# Regelaar.net
KiCad netlist of a schematic drawn in Altium Designer
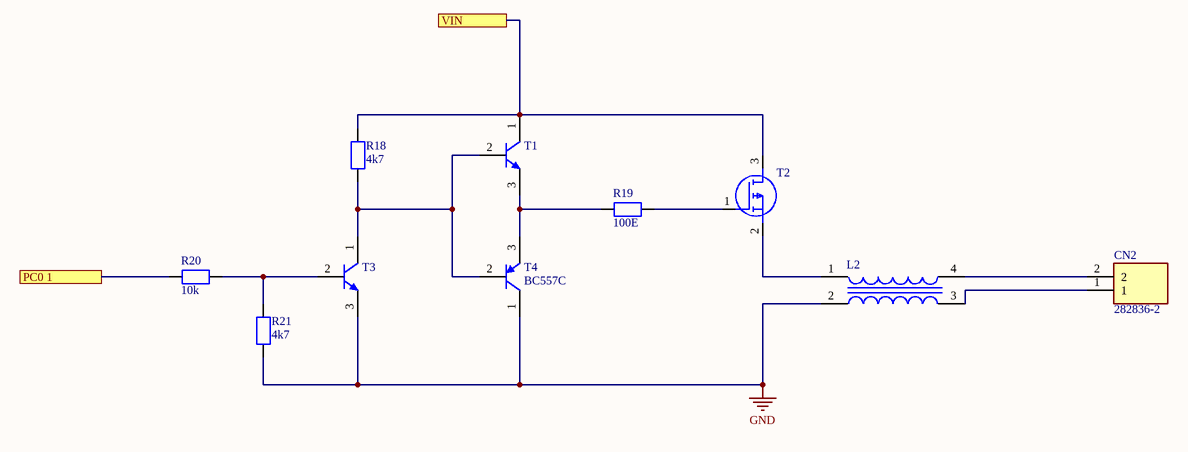
[diagram p0: Regelaar.SchDoc]

(export (version "E")
  (design (tool "Eeschema 10.0.6"))
  (components
    (comp (ref "CN2")
      (value "282836-2")
      (footprint "Schroefconnector 2 Pin")
      (description "Connector")
      (libsource (lib "Soldeerstation") (part "Schroefconnector 2 Pin L"))
    )
    (comp (ref "L2")
      (value "Smoorspoel commom mode")
      (footprint "smoorspoel Common mode")
      (description "Transformer CM2545X171B-10")
      (fields (field (name "MANUFACTURER_PART_NUMBER") "CM2545X171B-10"))
      (libsource (lib "Soldeerstation") (part "Smoorspoel commom mode"))
    )
    (comp (ref "R18")
      (value "4k7")
      (footprint "Resistor")
      (description "Resistor")
      (fields (field (name "MANUFACTURER") "Vishay Dale") (field (name "PART NUMBER") "CRCW08050000Z0EA"))
      (libsource (lib "Soldeerstation") (part "Resistor"))
    )
    (comp (ref "R19")
      (value "100E")
      (footprint "Resistor")
      (description "Resistor")
      (fields (field (name "MANUFACTURER") "Vishay Dale") (field (name "PART NUMBER") "CRCW08050000Z0EA"))
      (libsource (lib "Soldeerstation") (part "Resistor"))
    )
    (comp (ref "R20")
      (value "10k")
      (footprint "Resistor")
      (description "Resistor")
      (fields (field (name "MANUFACTURER") "Vishay Dale") (field (name "PART NUMBER") "CRCW08050000Z0EA"))
      (libsource (lib "Soldeerstation") (part "Resistor"))
    )
    (comp (ref "R21")
      (value "4k7")
      (footprint "Resistor")
      (description "Resistor")
      (fields (field (name "MANUFACTURER") "Vishay Dale") (field (name "PART NUMBER") "CRCW08050000Z0EA"))
      (libsource (lib "Soldeerstation") (part "Resistor"))
    )
    (comp (ref "T1")
      (value "BC547CZL1G")
      (footprint "BC547C")
      (description "BC547C, 45 V, 100 mA, 500 mW,\r\nhfe = 400")
      (fields (field (name "MANUFACTURER") "On Semiconductor"))
      (libsource (lib "Soldeerstation") (part "BC547C"))
    )
    (comp (ref "T2")
      (value "MOSFET")
      (footprint "MOSFET")
      (description "P-MOSFET, 55 V, 17 A,\r\n100 mΩ")
      (libsource (lib "Soldeerstation") (part "MOSFET"))
    )
    (comp (ref "T3")
      (value "BC547CZL1G")
      (footprint "BC547C")
      (description "BC547C, 45 V, 100 mA, 500 mW,\r\nhfe = 400")
      (fields (field (name "MANUFACTURER") "On Semiconductor"))
      (libsource (lib "Soldeerstation") (part "BC547C"))
    )
    (comp (ref "T4")
      (value "BC557C")
      (footprint "BC557C")
      (description "45 V, –100 mA, 500 mW,\r\nhfe = 400")
      (fields (field (name "MANUFACTURER") "On Semiconductor"))
      (libsource (lib "Soldeerstation") (part "BC557C"))
    )
  )
  (nets
    (net (code "1") (name "/PC0 1") (class "Default") (node (ref "R20") (pin "1") (pintype "passive")))
    (net (code "2") (name "/VIN") (class "Default")
      (node (ref "R18") (pin "2") (pinfunction "2_2") (pintype "passive"))
      (node (ref "T1") (pin "1") (pinfunction "C_1") (pintype "passive"))
      (node (ref "T2") (pin "3") (pinfunction "D_3") (pintype "passive"))
    )
    (net (code "3") (name "GND") (class "Default")
      (node (ref "L2") (pin "2") (pinfunction "SEC+_2") (pintype "passive"))
      (node (ref "R21") (pin "1") (pintype "passive"))
      (node (ref "T3") (pin "3") (pinfunction "E_3") (pintype "passive"))
      (node (ref "T4") (pin "1") (pinfunction "C_1") (pintype "passive"))
    )
    (net (code "4") (name "Net-(L2-PRI+)") (class "Default")
      (node (ref "L2") (pin "1") (pinfunction "PRI+_1") (pintype "passive"))
      (node (ref "T2") (pin "2") (pinfunction "S_2") (pintype "passive"))
    )
    (net (code "5") (name "Net-(L2-PRI-)") (class "Default")
      (node (ref "CN2") (pin "2") (pinfunction "2_2") (pintype "passive"))
      (node (ref "L2") (pin "4") (pinfunction "PRI-_4") (pintype "passive"))
    )
    (net (code "6") (name "Net-(L2-SEC-)") (class "Default")
      (node (ref "CN2") (pin "1") (pinfunction "1_1") (pintype "passive"))
      (node (ref "L2") (pin "3") (pinfunction "SEC-_3") (pintype "passive"))
    )
    (net (code "7") (name "Net-(T1-B)") (class "Default")
      (node (ref "R18") (pin "1") (pintype "passive"))
      (node (ref "T1") (pin "2") (pinfunction "B_2") (pintype "passive"))
      (node (ref "T3") (pin "1") (pinfunction "C_1") (pintype "passive"))
      (node (ref "T4") (pin "2") (pinfunction "B_2") (pintype "passive"))
    )
    (net (code "8") (name "Net-(T1-E)") (class "Default")
      (node (ref "R19") (pin "1") (pintype "passive"))
      (node (ref "T1") (pin "3") (pinfunction "E_3") (pintype "passive"))
      (node (ref "T4") (pin "3") (pinfunction "E_3") (pintype "passive"))
    )
    (net (code "9") (name "Net-(T2-G)") (class "Default")
      (node (ref "R19") (pin "2") (pinfunction "2_2") (pintype "passive"))
      (node (ref "T2") (pin "1") (pinfunction "G_1") (pintype "passive"))
    )
    (net (code "10") (name "Net-(T3-B)") (class "Default")
      (node (ref "R20") (pin "2") (pinfunction "2_2") (pintype "passive"))
      (node (ref "R21") (pin "2") (pinfunction "2_2") (pintype "passive"))
      (node (ref "T3") (pin "2") (pinfunction "B_2") (pintype "passive"))
    )
  )
)
